# remote.net
KiCad netlist of a schematic drawn in Altium Designer
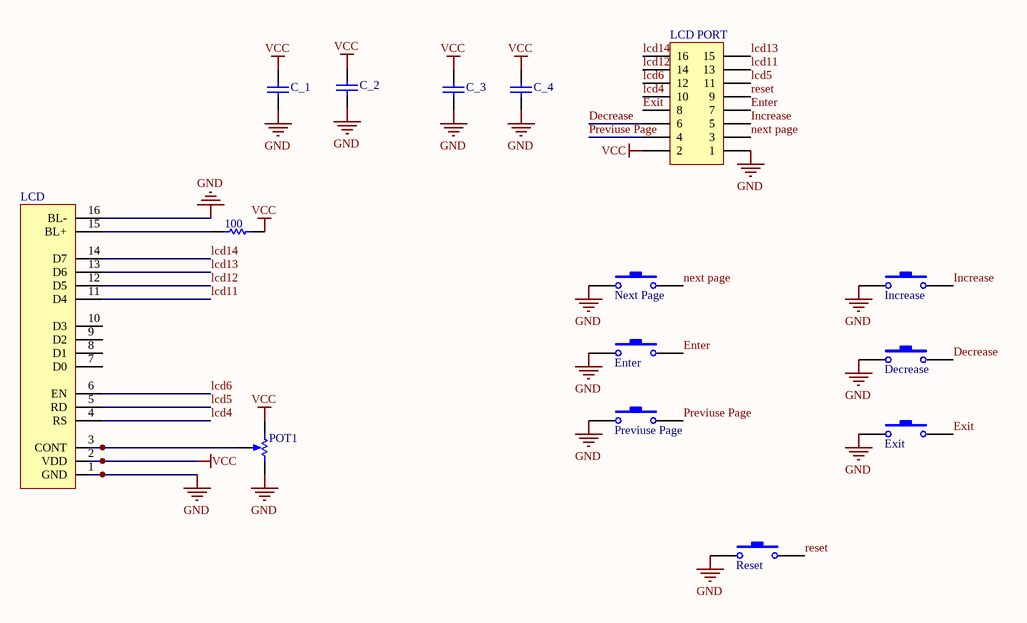
[diagram p0: remote.SchDoc]

(export (version "E")
  (design (tool "Eeschema 10.0.6"))
  (components
    (comp (ref "C_1")
      (value "100nF")
      (footprint "CAP 1206")
      (description "Capacitor")
      (fields (field (name "PUBLISHER") "Altium Limited"))
      (libsource (lib "My Parts 3d") (part "Cap"))
    )
    (comp (ref "C_2")
      (value "100nF")
      (footprint "CAP 1206")
      (description "Capacitor")
      (fields (field (name "PUBLISHER") "Altium Limited"))
      (libsource (lib "My Parts 3d") (part "Cap"))
    )
    (comp (ref "C_3")
      (value "100nF")
      (footprint "CAP 2")
      (description "Capacitor")
      (fields (field (name "PUBLISHER") "Altium Limited"))
      (libsource (lib "My Parts 3d") (part "Cap"))
    )
    (comp (ref "C_4")
      (value "100nF")
      (footprint "CAP 2")
      (description "Capacitor")
      (fields (field (name "PUBLISHER") "Altium Limited"))
      (libsource (lib "My Parts 3d") (part "Cap"))
    )
    (comp (ref "LCD")
      (value "LCD 1")
      (footprint "LCD 4X20 BLUE")
      (description "Header, 16-Pin, Dual row")
      (fields (field (name "PUBLISHER") "Altium Limited"))
      (libsource (lib "My Parts 3d") (part "LCD 1"))
    )
    (comp (ref "LCD PORT")
      (value "LCD PORT")
      (footprint "CON IDC 2X8")
      (description "Header, 8-Pin, Dual row")
      (fields (field (name "PUBLISHER") "Altium Limited"))
      (libsource (lib "My Parts 3d") (part "Header 8X2"))
    )
    (comp (ref "PB1")
      (value "Next Page")
      (footprint "push button 4")
      (description "Switch")
      (fields (field (name "PUBLISHER") "Altium Limited"))
      (libsource (lib "My Parts 3d") (part "PUSH BUTTON"))
    )
    (comp (ref "PB2")
      (value "Enter")
      (footprint "push button 4")
      (description "Switch")
      (fields (field (name "PUBLISHER") "Altium Limited"))
      (libsource (lib "My Parts 3d") (part "PUSH BUTTON"))
    )
    (comp (ref "PB3")
      (value "Previuse Page")
      (footprint "push button 4")
      (description "Switch")
      (fields (field (name "PUBLISHER") "Altium Limited"))
      (libsource (lib "My Parts 3d") (part "PUSH BUTTON"))
    )
    (comp (ref "PB4")
      (value "Increase")
      (footprint "PUSH BUTTON 4")
      (description "Switch")
      (fields (field (name "PUBLISHER") "Altium Limited"))
      (libsource (lib "My Parts 3d") (part "PUSH BUTTON"))
    )
    (comp (ref "PB5")
      (value "Decrease")
      (footprint "push button 4")
      (description "Switch")
      (fields (field (name "PUBLISHER") "Altium Limited"))
      (libsource (lib "My Parts 3d") (part "PUSH BUTTON"))
    )
    (comp (ref "PB6")
      (value "Reset")
      (footprint "push button 4")
      (description "Switch")
      (fields (field (name "PUBLISHER") "Altium Limited"))
      (libsource (lib "My Parts 3d") (part "PUSH BUTTON"))
    )
    (comp (ref "PB7")
      (value "Exit")
      (footprint "push button 4")
      (description "Switch")
      (fields (field (name "PUBLISHER") "Altium Limited"))
      (libsource (lib "My Parts 3d") (part "PUSH BUTTON"))
    )
    (comp (ref "POT1")
      (value "10K")
      (footprint "Multi Turn 01")
      (description "Potentiometer")
      (fields (field (name "PUBLISHER") "Altium Limited"))
      (libsource (lib "My Parts 3d") (part "RPot"))
    )
    (comp (ref "R3")
      (value "100")
      (footprint "res 1206")
      (description "Resistor")
      (fields (field (name "PUBLISHER") "Altium Limited"))
      (libsource (lib "Miscellaneous Devices") (part "Res1"))
    )
  )
  (nets
    (net (code "1") (name "/Decrease") (class "Default")
      (node (ref "LCD PORT") (pin "6") (pinfunction "6_6") (pintype "passive"))
      (node (ref "PB5") (pin "2") (pinfunction "2_2") (pintype "passive"))
    )
    (net (code "2") (name "/Enter") (class "Default")
      (node (ref "LCD PORT") (pin "7") (pinfunction "7_7") (pintype "passive"))
      (node (ref "PB2") (pin "2") (pinfunction "2_2") (pintype "passive"))
    )
    (net (code "3") (name "/Exit") (class "Default")
      (node (ref "LCD PORT") (pin "8") (pinfunction "8_8") (pintype "passive"))
      (node (ref "PB7") (pin "2") (pinfunction "2_2") (pintype "passive"))
    )
    (net (code "4") (name "/Increase") (class "Default")
      (node (ref "LCD PORT") (pin "5") (pinfunction "5_5") (pintype "passive"))
      (node (ref "PB4") (pin "2") (pinfunction "2_2") (pintype "passive"))
    )
    (net (code "5") (name "/Previuse Page") (class "Default")
      (node (ref "LCD PORT") (pin "4") (pinfunction "4_4") (pintype "passive"))
      (node (ref "PB3") (pin "2") (pinfunction "2_2") (pintype "passive"))
    )
    (net (code "6") (name "/lcd4") (class "Default")
      (node (ref "LCD") (pin "4") (pinfunction "RS_4") (pintype "passive"))
      (node (ref "LCD PORT") (pin "10") (pinfunction "10_10") (pintype "passive"))
    )
    (net (code "7") (name "/lcd5") (class "Default")
      (node (ref "LCD") (pin "5") (pinfunction "RD_5") (pintype "passive"))
      (node (ref "LCD PORT") (pin "11") (pinfunction "11_11") (pintype "passive"))
    )
    (net (code "8") (name "/lcd6") (class "Default")
      (node (ref "LCD") (pin "6") (pinfunction "EN_6") (pintype "passive"))
      (node (ref "LCD PORT") (pin "12") (pinfunction "12_12") (pintype "passive"))
    )
    (net (code "9") (name "/lcd11") (class "Default")
      (node (ref "LCD") (pin "11") (pinfunction "D4_11") (pintype "passive"))
      (node (ref "LCD PORT") (pin "13") (pinfunction "13_13") (pintype "passive"))
    )
    (net (code "10") (name "/lcd12") (class "Default")
      (node (ref "LCD") (pin "12") (pinfunction "D5_12") (pintype "passive"))
      (node (ref "LCD PORT") (pin "14") (pinfunction "14_14") (pintype "passive"))
    )
    (net (code "11") (name "/lcd13") (class "Default")
      (node (ref "LCD") (pin "13") (pinfunction "D6_13") (pintype "passive"))
      (node (ref "LCD PORT") (pin "15") (pinfunction "15_15") (pintype "passive"))
    )
    (net (code "12") (name "/lcd14") (class "Default")
      (node (ref "LCD") (pin "14") (pinfunction "D7_14") (pintype "passive"))
      (node (ref "LCD PORT") (pin "16") (pinfunction "16_16") (pintype "passive"))
    )
    (net (code "13") (name "/next page") (class "Default")
      (node (ref "LCD PORT") (pin "3") (pinfunction "3_3") (pintype "passive"))
      (node (ref "PB1") (pin "2") (pinfunction "2_2") (pintype "passive"))
    )
    (net (code "14") (name "/reset") (class "Default")
      (node (ref "LCD PORT") (pin "9") (pinfunction "9_9") (pintype "passive"))
      (node (ref "PB6") (pin "2") (pinfunction "2_2") (pintype "passive"))
    )
    (net (code "15") (name "GND") (class "Default")
      (node (ref "C_1") (pin "1") (pinfunction "1_1") (pintype "passive"))
      (node (ref "C_2") (pin "1") (pinfunction "1_1") (pintype "passive"))
      (node (ref "C_3") (pin "1") (pinfunction "1_1") (pintype "passive"))
      (node (ref "C_4") (pin "1") (pinfunction "1_1") (pintype "passive"))
      (node (ref "LCD") (pin "1") (pinfunction "GND_1") (pintype "passive"))
      (node (ref "LCD") (pin "16") (pinfunction "BL-_16") (pintype "passive"))
      (node (ref "LCD PORT") (pin "1") (pinfunction "1_1") (pintype "passive"))
      (node (ref "PB1") (pin "1") (pinfunction "1_1") (pintype "passive"))
      (node (ref "PB2") (pin "1") (pinfunction "1_1") (pintype "passive"))
      (node (ref "PB3") (pin "1") (pinfunction "1_1") (pintype "passive"))
      (node (ref "PB4") (pin "1") (pinfunction "1_1") (pintype "passive"))
      (node (ref "PB5") (pin "1") (pinfunction "1_1") (pintype "passive"))
      (node (ref "PB6") (pin "1") (pinfunction "1_1") (pintype "passive"))
      (node (ref "PB7") (pin "1") (pinfunction "1_1") (pintype "passive"))
      (node (ref "POT1") (pin "3") (pinfunction "BOT_3") (pintype "passive"))
    )
    (net (code "16") (name "Net-(LCD-BL+)") (class "Default")
      (node (ref "LCD") (pin "15") (pinfunction "BL+_15") (pintype "passive"))
      (node (ref "R3") (pin "2") (pinfunction "2_2") (pintype "passive"))
    )
    (net (code "17") (name "Net-(LCD-CONT)") (class "Default")
      (node (ref "LCD") (pin "3") (pinfunction "CONT_3") (pintype "passive"))
      (node (ref "POT1") (pin "2") (pinfunction "TAP_2") (pintype "passive"))
    )
    (net (code "18") (name "VCC") (class "Default")
      (node (ref "C_1") (pin "2") (pinfunction "2_2") (pintype "passive"))
      (node (ref "C_2") (pin "2") (pinfunction "2_2") (pintype "passive"))
      (node (ref "C_3") (pin "2") (pinfunction "2_2") (pintype "passive"))
      (node (ref "C_4") (pin "2") (pinfunction "2_2") (pintype "passive"))
      (node (ref "LCD") (pin "2") (pinfunction "VDD_2") (pintype "passive"))
      (node (ref "LCD PORT") (pin "2") (pinfunction "2_2") (pintype "passive"))
      (node (ref "POT1") (pin "1") (pinfunction "TOP_1") (pintype "passive"))
      (node (ref "R3") (pin "1") (pinfunction "1_1") (pintype "passive"))
    )
    (net (code "19") (name "unconnected-(LCD-D0-Pad7)") (class "Default")
      (node (ref "LCD") (pin "7") (pinfunction "D0_7") (pintype "passive"))
    )
    (net (code "20") (name "unconnected-(LCD-D1-Pad8)") (class "Default")
      (node (ref "LCD") (pin "8") (pinfunction "D1_8") (pintype "passive"))
    )
    (net (code "21") (name "unconnected-(LCD-D2-Pad9)") (class "Default")
      (node (ref "LCD") (pin "9") (pinfunction "D2_9") (pintype "passive"))
    )
    (net (code "22") (name "unconnected-(LCD-D3-Pad10)") (class "Default")
      (node (ref "LCD") (pin "10") (pinfunction "D3_10") (pintype "passive"))
    )
  )
)
